# Adafruit_Monochrome_1_12in_128x128_OLED.net
KiCad netlist of a schematic drawn in EAGLE
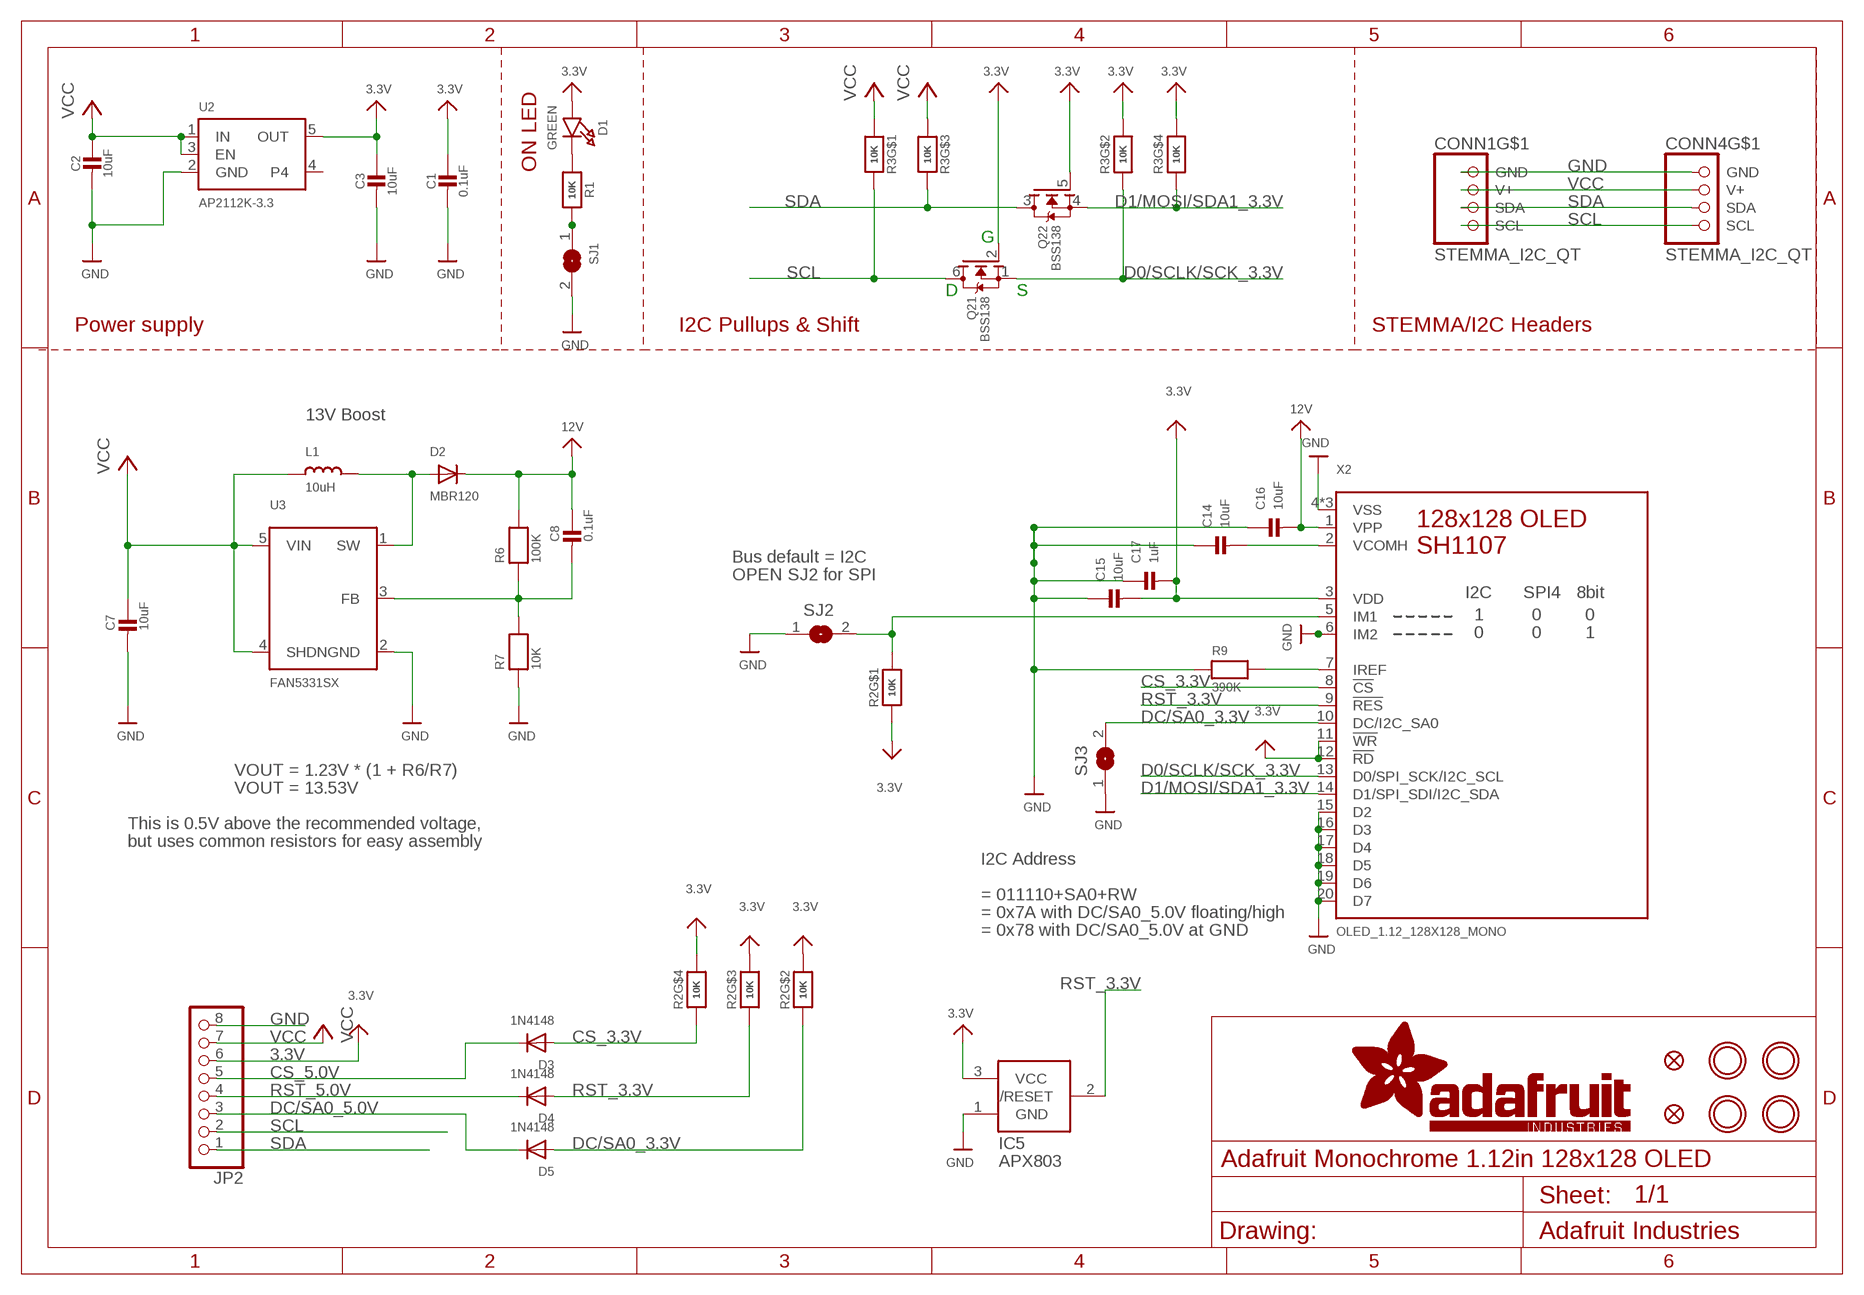
[diagram p0: schematic, sheet 1]

(export (version "E")
  (design (tool "Eeschema 10.0.6"))
  (components
    (comp (ref "C1")
      (value "0.1uF")
      (footprint "eagle-import:0603-NO")
      (libsource (lib "eagle-import") (part "CAP_CERAMIC0603_NO"))
    )
    (comp (ref "C2")
      (value "10uF")
      (footprint "eagle-import:0805-NO")
      (libsource (lib "eagle-import") (part "CAP_CERAMIC0805-NOOUTLINE"))
    )
    (comp (ref "C3")
      (value "10uF")
      (footprint "eagle-import:0805-NO")
      (libsource (lib "eagle-import") (part "CAP_CERAMIC0805-NOOUTLINE"))
    )
    (comp (ref "C7")
      (value "10uF")
      (footprint "eagle-import:0805-NO")
      (libsource (lib "eagle-import") (part "CAP_CERAMIC0805-NOOUTLINE"))
    )
    (comp (ref "C8")
      (value "0.1uF")
      (footprint "eagle-import:0603-NO")
      (libsource (lib "eagle-import") (part "CAP_CERAMIC0603_NO"))
    )
    (comp (ref "C14")
      (value "10uF")
      (footprint "eagle-import:0805-NO")
      (libsource (lib "eagle-import") (part "CAP_CERAMIC0805-NOOUTLINE"))
    )
    (comp (ref "C15")
      (value "10uF")
      (footprint "eagle-import:0805-NO")
      (libsource (lib "eagle-import") (part "CAP_CERAMIC0805-NOOUTLINE"))
    )
    (comp (ref "C16")
      (value "10uF")
      (footprint "eagle-import:0805-NO")
      (libsource (lib "eagle-import") (part "CAP_CERAMIC0805-NOOUTLINE"))
    )
    (comp (ref "C17")
      (value "1uF")
      (footprint "eagle-import:0603-NO")
      (libsource (lib "eagle-import") (part "CAP_CERAMIC0603_NO"))
    )
    (comp (ref "CONN1")
      (value "STEMMA_I2C_QT")
      (footprint "eagle-import:JST_SH4")
      (libsource (lib "eagle-import") (part "STEMMA_I2C_QT"))
    )
    (comp (ref "CONN4")
      (value "STEMMA_I2C_QT")
      (footprint "eagle-import:JST_SH4")
      (libsource (lib "eagle-import") (part "STEMMA_I2C_QT"))
    )
    (comp (ref "D1")
      (value "GREEN")
      (footprint "eagle-import:CHIPLED_0603_NOOUTLINE")
      (libsource (lib "eagle-import") (part "LED0603_NOOUTLINE"))
    )
    (comp (ref "D2")
      (value "MBR120")
      (footprint "eagle-import:SOD-123")
      (libsource (lib "eagle-import") (part "DIODESOD-123"))
    )
    (comp (ref "D3")
      (value "1N4148")
      (footprint "eagle-import:SOD-323")
      (libsource (lib "eagle-import") (part "DIODESOD-323"))
    )
    (comp (ref "D4")
      (value "1N4148")
      (footprint "eagle-import:SOD-323")
      (libsource (lib "eagle-import") (part "DIODESOD-323"))
    )
    (comp (ref "D5")
      (value "1N4148")
      (footprint "eagle-import:SOD-323")
      (libsource (lib "eagle-import") (part "DIODESOD-323"))
    )
    (comp (ref "FID3")
      (value "FIDUCIAL_1MM")
      (footprint "eagle-import:FIDUCIAL_1MM")
      (libsource (lib "eagle-import") (part "FIDUCIAL_1MM"))
    )
    (comp (ref "FID4")
      (value "FIDUCIAL_1MM")
      (footprint "eagle-import:FIDUCIAL_1MM")
      (libsource (lib "eagle-import") (part "FIDUCIAL_1MM"))
    )
    (comp (ref "IC5")
      (value "APX803")
      (footprint "eagle-import:SOT23")
      (libsource (lib "eagle-import") (part "AXP083-SAG"))
    )
    (comp (ref "JP2")
      (value "HEADER-1X876MIL")
      (footprint "eagle-import:1X08_ROUND_76")
      (libsource (lib "eagle-import") (part "HEADER-1X876MIL"))
    )
    (comp (ref "L1")
      (value "10uH")
      (footprint "eagle-import:INDUCTOR_1007")
      (libsource (lib "eagle-import") (part "INDUCTOR"))
    )
    (comp (ref "Q2")
      (value "BSS138")
      (footprint "eagle-import:SOT363")
      (libsource (lib "eagle-import") (part "MOSFET-N_DUAL"))
    )
    (comp (ref "R1")
      (value "10K")
      (footprint "eagle-import:0603-NO")
      (libsource (lib "eagle-import") (part "RESISTOR_0603_NOOUT"))
    )
    (comp (ref "R2")
      (value "10K")
      (footprint "eagle-import:RESPACK_4X0603")
      (libsource (lib "eagle-import") (part "RESISTOR_4PACK"))
    )
    (comp (ref "R3")
      (value "10K")
      (footprint "eagle-import:RESPACK_4X0603")
      (libsource (lib "eagle-import") (part "RESISTOR_4PACK"))
    )
    (comp (ref "R6")
      (value "100K")
      (footprint "eagle-import:0603-NO")
      (libsource (lib "eagle-import") (part "RESISTOR_0603_NOOUT"))
    )
    (comp (ref "R7")
      (value "10K")
      (footprint "eagle-import:0603-NO")
      (libsource (lib "eagle-import") (part "RESISTOR_0603_NOOUT"))
    )
    (comp (ref "R9")
      (value "390K")
      (footprint "eagle-import:0603-NO")
      (libsource (lib "eagle-import") (part "RESISTOR_0603_NOOUT"))
    )
    (comp (ref "SJ1")
      (value "SOLDERJUMPERCLOSED")
      (footprint "eagle-import:SOLDERJUMPER_CLOSEDWIRE")
      (libsource (lib "eagle-import") (part "SOLDERJUMPERCLOSED"))
    )
    (comp (ref "SJ2")
      (value "SOLDERJUMPER")
      (footprint "eagle-import:SOLDERJUMPER_ARROW_NOPASTE")
      (libsource (lib "eagle-import") (part "SOLDERJUMPER"))
    )
    (comp (ref "SJ3")
      (value "SOLDERJUMPER")
      (footprint "eagle-import:SOLDERJUMPER_ARROW_NOPASTE")
      (libsource (lib "eagle-import") (part "SOLDERJUMPER"))
    )
    (comp (ref "U$1")
      (value "MOUNTINGHOLE3.0THIN")
      (footprint "eagle-import:MOUNTINGHOLE_3.0_PLATEDTHIN")
      (libsource (lib "eagle-import") (part "MOUNTINGHOLE3.0THIN"))
    )
    (comp (ref "U$17")
      (value "MOUNTINGHOLE3.0THIN")
      (footprint "eagle-import:MOUNTINGHOLE_3.0_PLATEDTHIN")
      (libsource (lib "eagle-import") (part "MOUNTINGHOLE3.0THIN"))
    )
    (comp (ref "U$19")
      (value "MOUNTINGHOLE3.0THIN")
      (footprint "eagle-import:MOUNTINGHOLE_3.0_PLATEDTHIN")
      (libsource (lib "eagle-import") (part "MOUNTINGHOLE3.0THIN"))
    )
    (comp (ref "U$21")
      (value "MOUNTINGHOLE3.0THIN")
      (footprint "eagle-import:MOUNTINGHOLE_3.0_PLATEDTHIN")
      (libsource (lib "eagle-import") (part "MOUNTINGHOLE3.0THIN"))
    )
    (comp (ref "U2")
      (value "AP2112K-3.3")
      (footprint "eagle-import:SOT23-5")
      (libsource (lib "eagle-import") (part "VREG_SOT23-5"))
    )
    (comp (ref "U3")
      (value "FAN5331SX")
      (footprint "eagle-import:SOT23-5@1")
      (libsource (lib "eagle-import") (part "FAN5331"))
    )
    (comp (ref "X2")
      (value "OLED_1.12_128X128_MONO")
      (footprint "eagle-import:OLED_1.12IN_128X128MONO")
      (libsource (lib "eagle-import") (part "OLED_1.12_128X128_MONO"))
    )
  )
  (nets
    (net (code "1") (name "/CS_3.3V") (class "Default")
      (node (ref "D3") (pin "A") (pinfunction "A_A") (pintype "passive"))
      (node (ref "R2") (pin "4") (pinfunction "1_4") (pintype "passive"))
      (node (ref "X2") (pin "8") (pinfunction "~{CS}_8") (pintype "input"))
    )
    (net (code "2") (name "/CS_5.0V") (class "Default")
      (node (ref "D3") (pin "C") (pinfunction "C_C") (pintype "passive"))
      (node (ref "JP2") (pin "5") (pinfunction "5_5") (pintype "passive"))
    )
    (net (code "3") (name "/D0{slash}SCLK{slash}SCK_3.3V") (class "Default")
      (node (ref "Q2") (pin "1") (pinfunction "S_1") (pintype "bidirectional"))
      (node (ref "R3") (pin "7") (pinfunction "2_7") (pintype "passive"))
      (node (ref "X2") (pin "13") (pinfunction "D0/SPI_SCK/I2C_SCL_13") (pintype "bidirectional"))
    )
    (net (code "4") (name "/D1{slash}MOSI{slash}SDA1_3.3V") (class "Default")
      (node (ref "Q2") (pin "4") (pinfunction "S_4") (pintype "bidirectional"))
      (node (ref "R3") (pin "5") (pinfunction "2_5") (pintype "passive"))
      (node (ref "X2") (pin "14") (pinfunction "D1/SPI_SDI/I2C_SDA_14") (pintype "bidirectional"))
    )
    (net (code "5") (name "/DC{slash}SA0_3.3V") (class "Default")
      (node (ref "D5") (pin "A") (pinfunction "A_A") (pintype "passive"))
      (node (ref "R2") (pin "2") (pinfunction "1_2") (pintype "passive"))
      (node (ref "SJ3") (pin "2") (pinfunction "2_2") (pintype "passive"))
      (node (ref "X2") (pin "10") (pinfunction "DC/I2C_SA0_10") (pintype "input"))
    )
    (net (code "6") (name "/DC{slash}SA0_5.0V") (class "Default")
      (node (ref "D5") (pin "C") (pinfunction "C_C") (pintype "passive"))
      (node (ref "JP2") (pin "3") (pinfunction "3_3") (pintype "passive"))
    )
    (net (code "7") (name "/RST_3.3V") (class "Default")
      (node (ref "D4") (pin "A") (pinfunction "A_A") (pintype "passive"))
      (node (ref "IC5") (pin "2") (pinfunction "/RESET_2") (pintype "output"))
      (node (ref "R2") (pin "3") (pinfunction "1_3") (pintype "passive"))
      (node (ref "X2") (pin "9") (pinfunction "~{RES}_9") (pintype "input"))
    )
    (net (code "8") (name "/RST_5.0V") (class "Default")
      (node (ref "D4") (pin "C") (pinfunction "C_C") (pintype "passive"))
      (node (ref "JP2") (pin "4") (pinfunction "4_4") (pintype "passive"))
    )
    (net (code "9") (name "/SCL") (class "Default")
      (node (ref "CONN1") (pin "4") (pinfunction "SCL_4") (pintype "passive"))
      (node (ref "CONN4") (pin "4") (pinfunction "SCL_4") (pintype "passive"))
      (node (ref "JP2") (pin "2") (pinfunction "2_2") (pintype "passive"))
      (node (ref "Q2") (pin "6") (pinfunction "D_6") (pintype "bidirectional"))
      (node (ref "R3") (pin "8") (pinfunction "2_8") (pintype "passive"))
    )
    (net (code "10") (name "/SDA") (class "Default")
      (node (ref "CONN1") (pin "3") (pinfunction "SDA_3") (pintype "passive"))
      (node (ref "CONN4") (pin "3") (pinfunction "SDA_3") (pintype "passive"))
      (node (ref "JP2") (pin "1") (pinfunction "1_1") (pintype "passive"))
      (node (ref "Q2") (pin "3") (pinfunction "D_3") (pintype "bidirectional"))
      (node (ref "R3") (pin "6") (pinfunction "2_6") (pintype "passive"))
    )
    (net (code "11") (name "3.3V") (class "Default")
      (node (ref "C1") (pin "1") (pinfunction "1_1") (pintype "passive"))
      (node (ref "C15") (pin "2") (pinfunction "2_2") (pintype "passive"))
      (node (ref "C17") (pin "2") (pinfunction "2_2") (pintype "passive"))
      (node (ref "C3") (pin "1") (pinfunction "1_1") (pintype "passive"))
      (node (ref "D1") (pin "A") (pinfunction "A_A") (pintype "passive"))
      (node (ref "IC5") (pin "3") (pinfunction "VCC_3") (pintype "power_in"))
      (node (ref "JP2") (pin "6") (pinfunction "6_6") (pintype "passive"))
      (node (ref "Q2") (pin "2") (pinfunction "G_2") (pintype "bidirectional"))
      (node (ref "Q2") (pin "5") (pinfunction "G_5") (pintype "bidirectional"))
      (node (ref "R2") (pin "1") (pinfunction "1_1") (pintype "passive"))
      (node (ref "R2") (pin "5") (pinfunction "2_5") (pintype "passive"))
      (node (ref "R2") (pin "6") (pinfunction "2_6") (pintype "passive"))
      (node (ref "R2") (pin "7") (pinfunction "2_7") (pintype "passive"))
      (node (ref "R3") (pin "2") (pinfunction "1_2") (pintype "passive"))
      (node (ref "R3") (pin "4") (pinfunction "1_4") (pintype "passive"))
      (node (ref "U2") (pin "5") (pinfunction "OUT_5") (pintype "power_in"))
      (node (ref "X2") (pin "11") (pinfunction "~{WR}_11") (pintype "input"))
      (node (ref "X2") (pin "12") (pinfunction "~{RD}_12") (pintype "input"))
      (node (ref "X2") (pin "3") (pinfunction "VDD_3") (pintype "power_in"))
    )
    (net (code "12") (name "12V") (class "Default")
      (node (ref "C16") (pin "2") (pinfunction "2_2") (pintype "passive"))
      (node (ref "C8") (pin "1") (pinfunction "1_1") (pintype "passive"))
      (node (ref "D2") (pin "C") (pinfunction "C_C") (pintype "passive"))
      (node (ref "R6") (pin "2") (pinfunction "2_2") (pintype "passive"))
      (node (ref "X2") (pin "1") (pinfunction "VPP_1") (pintype "power_in"))
    )
    (net (code "13") (name "GND") (class "Default")
      (node (ref "C1") (pin "2") (pinfunction "2_2") (pintype "passive"))
      (node (ref "C14") (pin "1") (pinfunction "1_1") (pintype "passive"))
      (node (ref "C15") (pin "1") (pinfunction "1_1") (pintype "passive"))
      (node (ref "C16") (pin "1") (pinfunction "1_1") (pintype "passive"))
      (node (ref "C17") (pin "1") (pinfunction "1_1") (pintype "passive"))
      (node (ref "C2") (pin "2") (pinfunction "2_2") (pintype "passive"))
      (node (ref "C3") (pin "2") (pinfunction "2_2") (pintype "passive"))
      (node (ref "C7") (pin "2") (pinfunction "2_2") (pintype "passive"))
      (node (ref "CONN1") (pin "1") (pinfunction "GND_1") (pintype "passive"))
      (node (ref "CONN4") (pin "1") (pinfunction "GND_1") (pintype "passive"))
      (node (ref "IC5") (pin "1") (pinfunction "GND_1") (pintype "power_in"))
      (node (ref "JP2") (pin "8") (pinfunction "8_8") (pintype "passive"))
      (node (ref "R7") (pin "1") (pinfunction "1_1") (pintype "passive"))
      (node (ref "R9") (pin "1") (pinfunction "1_1") (pintype "passive"))
      (node (ref "SJ1") (pin "2") (pinfunction "2_2") (pintype "passive"))
      (node (ref "SJ2") (pin "1") (pinfunction "1_1") (pintype "passive"))
      (node (ref "SJ3") (pin "1") (pinfunction "1_1") (pintype "passive"))
      (node (ref "U2") (pin "2") (pinfunction "GND_2") (pintype "power_in"))
      (node (ref "U3") (pin "2") (pinfunction "GND_2") (pintype "bidirectional"))
      (node (ref "X2") (pin "15") (pinfunction "D2_15") (pintype "bidirectional"))
      (node (ref "X2") (pin "16") (pinfunction "D3_16") (pintype "bidirectional"))
      (node (ref "X2") (pin "17") (pinfunction "D4_17") (pintype "bidirectional"))
      (node (ref "X2") (pin "18") (pinfunction "D5_18") (pintype "bidirectional"))
      (node (ref "X2") (pin "19") (pinfunction "D6_19") (pintype "bidirectional"))
      (node (ref "X2") (pin "20") (pinfunction "D7_20") (pintype "bidirectional"))
      (node (ref "X2") (pin "21") (pinfunction "VSS_21") (pintype "power_in"))
      (node (ref "X2") (pin "22") (pinfunction "VSS_22") (pintype "power_in"))
      (node (ref "X2") (pin "4") (pinfunction "VSS_4") (pintype "power_in"))
      (node (ref "X2") (pin "6") (pinfunction "IM2_6") (pintype "input"))
    )
    (net (code "14") (name "Net-(D1-PadC)") (class "Default")
      (node (ref "D1") (pin "C") (pinfunction "C_C") (pintype "passive"))
      (node (ref "R1") (pin "1") (pinfunction "1_1") (pintype "passive"))
    )
    (net (code "15") (name "Net-(L1-2)") (class "Default")
      (node (ref "D2") (pin "A") (pinfunction "A_A") (pintype "passive"))
      (node (ref "L1") (pin "P$2") (pinfunction "2_P$2") (pintype "passive"))
      (node (ref "U3") (pin "1") (pinfunction "SW_1") (pintype "bidirectional"))
    )
    (net (code "16") (name "Net-(R1-Pad2)") (class "Default")
      (node (ref "R1") (pin "2") (pinfunction "2_2") (pintype "passive"))
      (node (ref "SJ1") (pin "1") (pinfunction "1_1") (pintype "passive"))
    )
    (net (code "17") (name "Net-(R2A-2)") (class "Default")
      (node (ref "R2") (pin "8") (pinfunction "2_8") (pintype "passive"))
      (node (ref "SJ2") (pin "2") (pinfunction "2_2") (pintype "passive"))
      (node (ref "X2") (pin "5") (pinfunction "IM1_5") (pintype "input"))
    )
    (net (code "18") (name "Net-(U3-FB)") (class "Default")
      (node (ref "C8") (pin "2") (pinfunction "2_2") (pintype "passive"))
      (node (ref "R6") (pin "1") (pinfunction "1_1") (pintype "passive"))
      (node (ref "R7") (pin "2") (pinfunction "2_2") (pintype "passive"))
      (node (ref "U3") (pin "3") (pinfunction "FB_3") (pintype "bidirectional"))
    )
    (net (code "19") (name "Net-(X2-IREF)") (class "Default")
      (node (ref "R9") (pin "2") (pinfunction "2_2") (pintype "passive"))
      (node (ref "X2") (pin "7") (pinfunction "IREF_7") (pintype "input"))
    )
    (net (code "20") (name "Net-(X2-VCOMH)") (class "Default")
      (node (ref "C14") (pin "2") (pinfunction "2_2") (pintype "passive"))
      (node (ref "X2") (pin "2") (pinfunction "VCOMH_2") (pintype "output"))
    )
    (net (code "21") (name "VCC") (class "Default")
      (node (ref "C2") (pin "1") (pinfunction "1_1") (pintype "passive"))
      (node (ref "C7") (pin "1") (pinfunction "1_1") (pintype "passive"))
      (node (ref "CONN1") (pin "2") (pinfunction "V+_2") (pintype "passive"))
      (node (ref "CONN4") (pin "2") (pinfunction "V+_2") (pintype "passive"))
      (node (ref "JP2") (pin "7") (pinfunction "7_7") (pintype "passive"))
      (node (ref "L1") (pin "P$1") (pinfunction "1_P$1") (pintype "passive"))
      (node (ref "R3") (pin "1") (pinfunction "1_1") (pintype "passive"))
      (node (ref "R3") (pin "3") (pinfunction "1_3") (pintype "passive"))
      (node (ref "U2") (pin "1") (pinfunction "IN_1") (pintype "power_in"))
      (node (ref "U2") (pin "3") (pinfunction "EN_3") (pintype "input"))
      (node (ref "U3") (pin "4") (pinfunction "SHDN_4") (pintype "bidirectional"))
      (node (ref "U3") (pin "5") (pinfunction "VIN_5") (pintype "bidirectional"))
    )
    (net (code "22") (name "unconnected-(U2-P4-Pad4)") (class "Default")
      (node (ref "U2") (pin "4") (pinfunction "P4_4") (pintype "bidirectional"))
    )
  )
)
